# LumiDrive.net
KiCad netlist of a schematic drawn in EAGLE
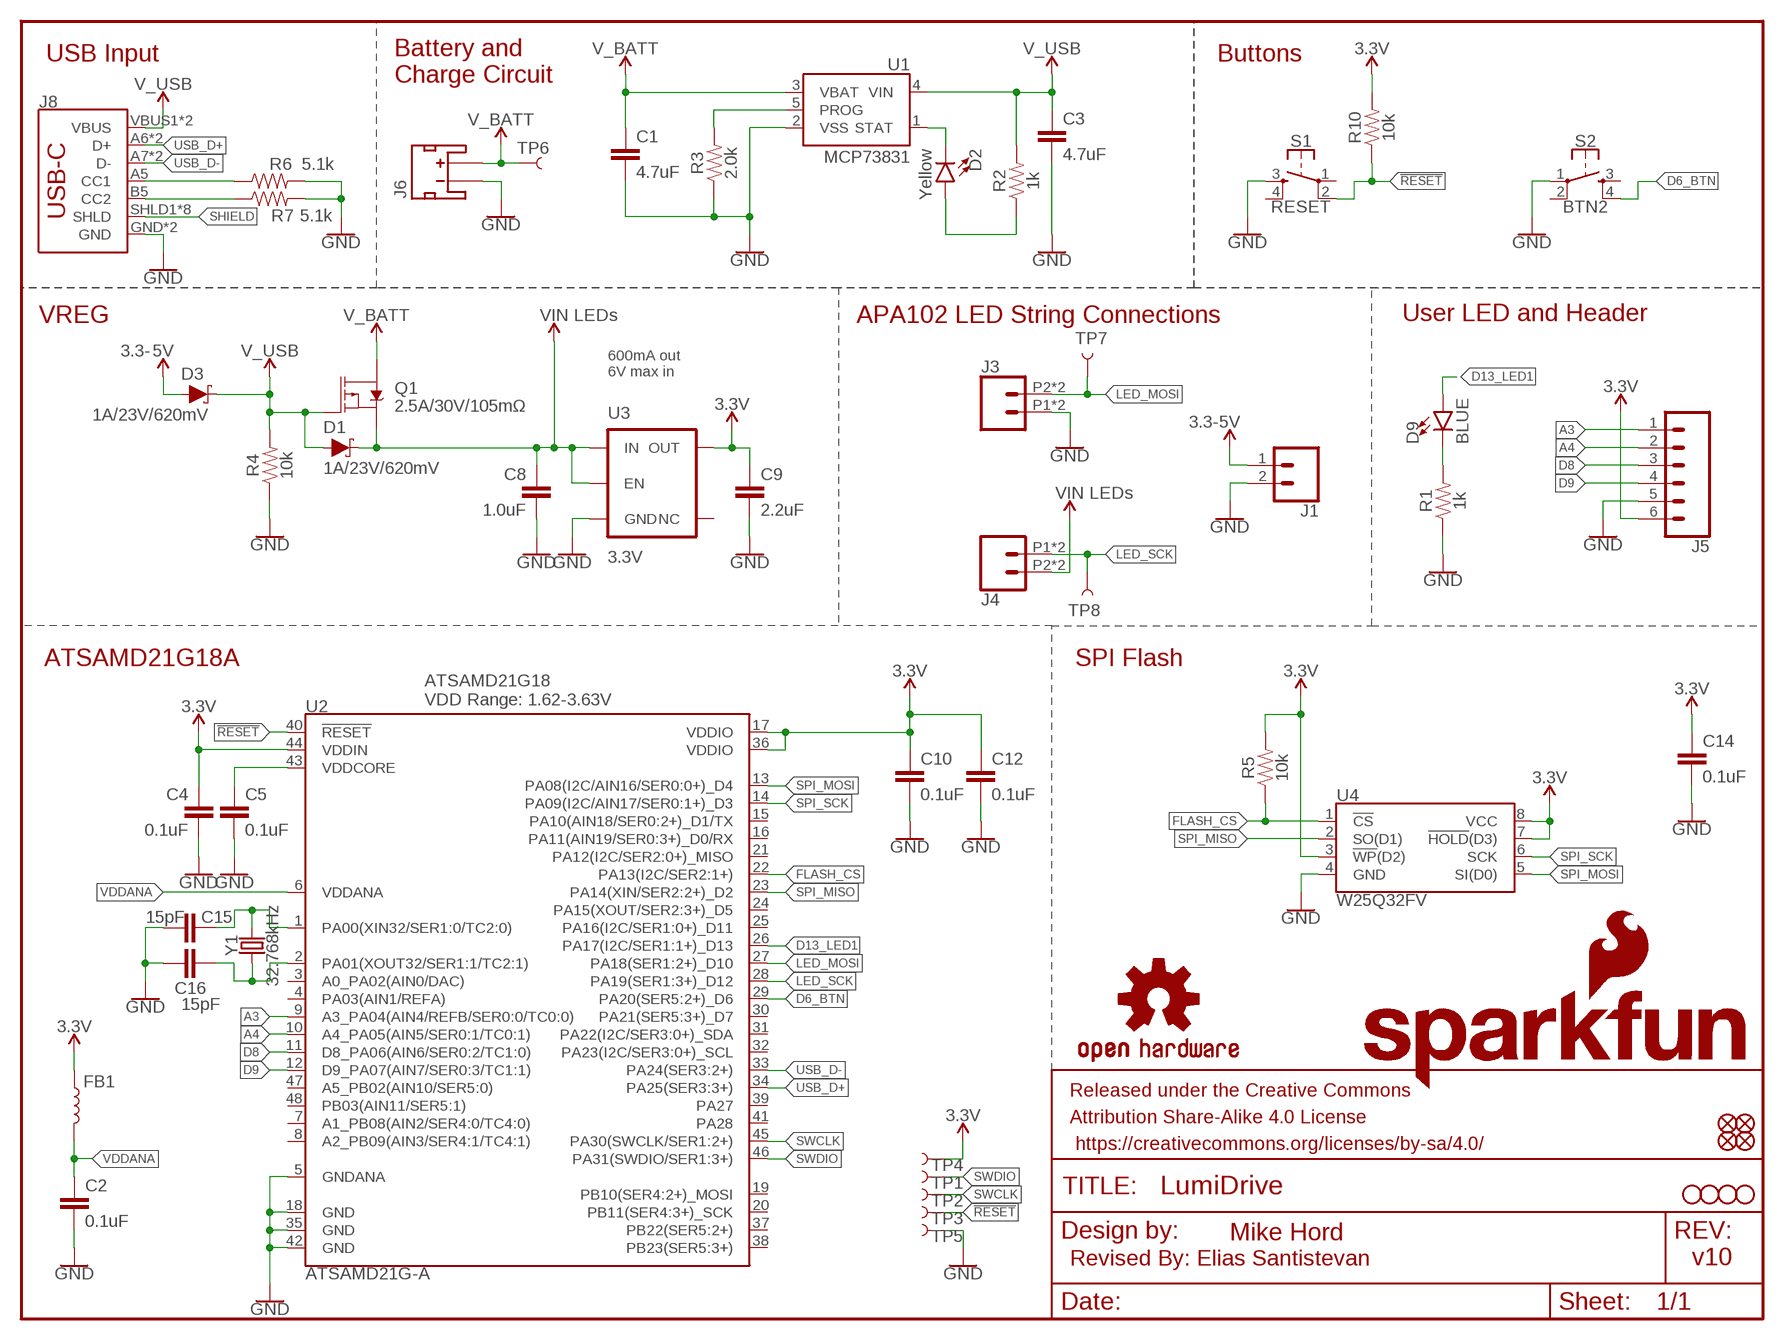
[diagram p0: schematic, sheet 1]

(export (version "E")
  (design (tool "Eeschema 10.0.6"))
  (components
    (comp (ref "C1")
      (value "4.7uF")
      (footprint "eagle-import:0603")
      (libsource (lib "eagle-import") (part "4.7UF-0603-6.3V-(10%)"))
    )
    (comp (ref "C2")
      (value "0.1uF")
      (footprint "eagle-import:0603")
      (libsource (lib "eagle-import") (part "0.1UF-0603-25V-(+80/-20%)"))
    )
    (comp (ref "C3")
      (value "4.7uF")
      (footprint "eagle-import:0603")
      (libsource (lib "eagle-import") (part "4.7UF-0603-6.3V-(10%)"))
    )
    (comp (ref "C4")
      (value "0.1uF")
      (footprint "eagle-import:0603")
      (libsource (lib "eagle-import") (part "0.1UF-0603-25V-(+80/-20%)"))
    )
    (comp (ref "C5")
      (value "0.1uF")
      (footprint "eagle-import:0603")
      (libsource (lib "eagle-import") (part "0.1UF-0603-25V-(+80/-20%)"))
    )
    (comp (ref "C8")
      (value "1.0uF")
      (footprint "eagle-import:0805")
      (libsource (lib "eagle-import") (part "1.0UF-0805-25V-10%"))
    )
    (comp (ref "C9")
      (value "2.2uF")
      (footprint "eagle-import:0603")
      (libsource (lib "eagle-import") (part "2.2UF-0603-10V-20%"))
    )
    (comp (ref "C10")
      (value "0.1uF")
      (footprint "eagle-import:0603")
      (libsource (lib "eagle-import") (part "0.1UF-0603-25V-(+80/-20%)"))
    )
    (comp (ref "C12")
      (value "0.1uF")
      (footprint "eagle-import:0603")
      (libsource (lib "eagle-import") (part "0.1UF-0603-25V-(+80/-20%)"))
    )
    (comp (ref "C14")
      (value "0.1uF")
      (footprint "eagle-import:0603")
      (libsource (lib "eagle-import") (part "0.1UF-0603-25V-(+80/-20%)"))
    )
    (comp (ref "C15")
      (value "15pF")
      (footprint "eagle-import:0603")
      (libsource (lib "eagle-import") (part "15PF-0603-50V-5%"))
    )
    (comp (ref "C16")
      (value "15pF")
      (footprint "eagle-import:0603")
      (libsource (lib "eagle-import") (part "15PF-0603-50V-5%"))
    )
    (comp (ref "D1")
      (value "1A/23V/620mV")
      (footprint "eagle-import:SOD-323")
      (libsource (lib "eagle-import") (part "DIODE-SCHOTTKY-BAT20J"))
    )
    (comp (ref "D2")
      (value "Yellow")
      (footprint "eagle-import:LED-0603")
      (libsource (lib "eagle-import") (part "LED-YELLOW0603"))
    )
    (comp (ref "D3")
      (value "1A/23V/620mV")
      (footprint "eagle-import:SOD-323")
      (libsource (lib "eagle-import") (part "DIODE-SCHOTTKY-BAT20J"))
    )
    (comp (ref "D9")
      (value "BLUE")
      (footprint "eagle-import:LED-0603")
      (libsource (lib "eagle-import") (part "LED-BLUE0603"))
    )
    (comp (ref "FB1")
      (value "30Ω/1.8A")
      (footprint "eagle-import:0603")
      (libsource (lib "eagle-import") (part "INDUCTORFB-30OHM"))
    )
    (comp (ref "FD1")
      (value "FIDUCIALUFIDUCIAL")
      (footprint "eagle-import:FIDUCIAL-MICRO")
      (libsource (lib "eagle-import") (part "FIDUCIALUFIDUCIAL"))
    )
    (comp (ref "FD2")
      (value "FIDUCIALUFIDUCIAL")
      (footprint "eagle-import:FIDUCIAL-MICRO")
      (libsource (lib "eagle-import") (part "FIDUCIALUFIDUCIAL"))
    )
    (comp (ref "FD3")
      (value "FIDUCIALUFIDUCIAL")
      (footprint "eagle-import:FIDUCIAL-MICRO")
      (libsource (lib "eagle-import") (part "FIDUCIALUFIDUCIAL"))
    )
    (comp (ref "FD4")
      (value "FIDUCIALUFIDUCIAL")
      (footprint "eagle-import:FIDUCIAL-MICRO")
      (libsource (lib "eagle-import") (part "FIDUCIALUFIDUCIAL"))
    )
    (comp (ref "FRAME1")
      (value "FRAME-LETTER")
      (footprint "eagle-import:CREATIVE_COMMONS")
      (libsource (lib "eagle-import") (part "FRAME-LETTER"))
    )
    (comp (ref "H1")
      (value "STAND-OFF")
      (footprint "eagle-import:STAND-OFF")
      (libsource (lib "eagle-import") (part "STAND-OFF"))
    )
    (comp (ref "H2")
      (value "STAND-OFF")
      (footprint "eagle-import:STAND-OFF")
      (libsource (lib "eagle-import") (part "STAND-OFF"))
    )
    (comp (ref "H3")
      (value "STAND-OFF")
      (footprint "eagle-import:STAND-OFF")
      (libsource (lib "eagle-import") (part "STAND-OFF"))
    )
    (comp (ref "H4")
      (value "STAND-OFF")
      (footprint "eagle-import:STAND-OFF")
      (libsource (lib "eagle-import") (part "STAND-OFF"))
    )
    (comp (ref "J1")
      (value "CONN_021X02_NO_SILK")
      (footprint "eagle-import:1X02_NO_SILK")
      (libsource (lib "eagle-import") (part "CONN_021X02_NO_SILK"))
    )
    (comp (ref "J3")
      (value "CONN_02SMALL_POKEHOME")
      (footprint "eagle-import:1X02_POKEHOME")
      (libsource (lib "eagle-import") (part "CONN_02SMALL_POKEHOME"))
    )
    (comp (ref "J4")
      (value "CONN_02SMALL_POKEHOME")
      (footprint "eagle-import:1X02_POKEHOME")
      (libsource (lib "eagle-import") (part "CONN_02SMALL_POKEHOME"))
    )
    (comp (ref "J5")
      (value "CONN_06NO_SILK_FEMALE_PTH")
      (footprint "eagle-import:1X06_NO_SILK")
      (libsource (lib "eagle-import") (part "CONN_06NO_SILK_FEMALE_PTH"))
    )
    (comp (ref "J6")
      (value "JST_2MM_MALE")
      (footprint "eagle-import:JST-2-SMD")
      (libsource (lib "eagle-import") (part "JST_2MM_MALE"))
    )
    (comp (ref "J8")
      (value "USB_C16PIN")
      (footprint "eagle-import:USB-C-16P")
      (libsource (lib "eagle-import") (part "USB_C16PIN"))
    )
    (comp (ref "LOGO1")
      (value "OSHW-LOGOM")
      (footprint "eagle-import:OSHW-LOGO-M")
      (libsource (lib "eagle-import") (part "OSHW-LOGOM"))
    )
    (comp (ref "LOGO3")
      (value "SFE_LOGO_NAME_FLAME.2_INCH")
      (footprint "eagle-import:SFE_LOGO_NAME_FLAME_.2")
      (libsource (lib "eagle-import") (part "SFE_LOGO_NAME_FLAME.2_INCH"))
    )
    (comp (ref "Q1")
      (value "2.5A/30V/105mΩ")
      (footprint "eagle-import:SOT23-3")
      (libsource (lib "eagle-import") (part "MOSFET_PCH-DMG2307L"))
    )
    (comp (ref "R1")
      (value "1k")
      (footprint "eagle-import:0603")
      (libsource (lib "eagle-import") (part "1KOHM-0603-1/10W-1%"))
    )
    (comp (ref "R2")
      (value "1k")
      (footprint "eagle-import:0603")
      (libsource (lib "eagle-import") (part "1KOHM-0603-1/10W-1%"))
    )
    (comp (ref "R3")
      (value "2.0k")
      (footprint "eagle-import:0603")
      (libsource (lib "eagle-import") (part "2.0KOHM-0603-1/10W-5%"))
    )
    (comp (ref "R4")
      (value "10k")
      (footprint "eagle-import:0603")
      (libsource (lib "eagle-import") (part "10KOHM-0603-1/10W-1%"))
    )
    (comp (ref "R5")
      (value "10k")
      (footprint "eagle-import:0603")
      (libsource (lib "eagle-import") (part "10KOHM-0603-1/10W-1%"))
    )
    (comp (ref "R6")
      (value "5.1k")
      (footprint "eagle-import:0603")
      (libsource (lib "eagle-import") (part "5.1KOHM5.1KOHM-0603-1/10W-1%"))
    )
    (comp (ref "R7")
      (value "5.1k")
      (footprint "eagle-import:0603")
      (libsource (lib "eagle-import") (part "5.1KOHM5.1KOHM-0603-1/10W-1%"))
    )
    (comp (ref "R10")
      (value "10k")
      (footprint "eagle-import:0603")
      (libsource (lib "eagle-import") (part "10KOHM-0603-1/10W-1%"))
    )
    (comp (ref "S1")
      (value "RESET")
      (footprint "eagle-import:TACTILE_SWITCH_SMD_4.6X2.8MM")
      (libsource (lib "eagle-import") (part "MOMENTARY-SWITCH-SPST-2-SMD-4.6X2.8MM"))
    )
    (comp (ref "S2")
      (value "BTN2")
      (footprint "eagle-import:TACTILE_SWITCH_SMD_4.6X2.8MM")
      (libsource (lib "eagle-import") (part "MOMENTARY-SWITCH-SPST-2-SMD-4.6X2.8MM"))
    )
    (comp (ref "TP1")
      (value "TP-SWDIO")
      (footprint "eagle-import:PAD.03X.05")
      (libsource (lib "eagle-import") (part "TEST-POINT3X5"))
    )
    (comp (ref "TP2")
      (value "TP-SWCLK")
      (footprint "eagle-import:PAD.03X.05")
      (libsource (lib "eagle-import") (part "TEST-POINT3X5"))
    )
    (comp (ref "TP3")
      (value "TP-!RESET!")
      (footprint "eagle-import:PAD.03X.05")
      (libsource (lib "eagle-import") (part "TEST-POINT3X5"))
    )
    (comp (ref "TP4")
      (value "TP-3.3V")
      (footprint "eagle-import:PAD.03X.05")
      (libsource (lib "eagle-import") (part "TEST-POINT3X5"))
    )
    (comp (ref "TP5")
      (value "TP-GND")
      (footprint "eagle-import:PAD.03X.05")
      (libsource (lib "eagle-import") (part "TEST-POINT3X5"))
    )
    (comp (ref "TP6")
      (value "TEST-POINT3X4")
      (footprint "eagle-import:PAD.03X.04")
      (libsource (lib "eagle-import") (part "TEST-POINT3X4"))
    )
    (comp (ref "TP7")
      (value "TEST-POINT3X4")
      (footprint "eagle-import:PAD.03X.04")
      (libsource (lib "eagle-import") (part "TEST-POINT3X4"))
    )
    (comp (ref "TP8")
      (value "TEST-POINT3X4")
      (footprint "eagle-import:PAD.03X.04")
      (libsource (lib "eagle-import") (part "TEST-POINT3X4"))
    )
    (comp (ref "U1")
      (value "MCP73831")
      (footprint "eagle-import:SOT23-5")
      (libsource (lib "eagle-import") (part "MCP73831"))
    )
    (comp (ref "U2")
      (value "ATSAMD21G-A")
      (footprint "eagle-import:TQFP-48")
      (libsource (lib "eagle-import") (part "ATSAMD21G-A"))
    )
    (comp (ref "U3")
      (value "3.3V")
      (footprint "eagle-import:SOT23-5")
      (fields (field (name "PROD_ID") "VREG-12457"))
      (libsource (lib "eagle-import") (part "V_REG_AP2112K-3.3V"))
    )
    (comp (ref "U4")
      (value "W25Q32FV")
      (footprint "eagle-import:SOIC-8")
      (libsource (lib "eagle-import") (part "W25Q32FVSS"))
    )
    (comp (ref "Y1")
      (value "32.768kHz")
      (footprint "eagle-import:CRYSTAL-SMD-3.2X1.5MM")
      (libsource (lib "eagle-import") (part "CRYSTAL-32.768KHZSMD-3.2X1.5"))
    )
  )
  (nets
    (net (code "1") (name "/~{RESET}") (class "Default")
      (node (ref "R10") (pin "1") (pinfunction "1_1") (pintype "passive"))
      (node (ref "S1") (pin "2") (pinfunction "2_2") (pintype "passive"))
      (node (ref "TP3") (pin "P$1") (pinfunction "1_P$1") (pintype "bidirectional"))
      (node (ref "U2") (pin "40") (pinfunction "~{RESET}_40") (pintype "bidirectional"))
    )
    (net (code "2") (name "3.3V") (class "Default")
      (node (ref "C10") (pin "1") (pinfunction "1_1") (pintype "passive"))
      (node (ref "C12") (pin "1") (pinfunction "1_1") (pintype "passive"))
      (node (ref "C14") (pin "1") (pinfunction "1_1") (pintype "passive"))
      (node (ref "C4") (pin "1") (pinfunction "1_1") (pintype "passive"))
      (node (ref "C9") (pin "1") (pinfunction "1_1") (pintype "passive"))
      (node (ref "FB1") (pin "1") (pinfunction "1_1") (pintype "passive"))
      (node (ref "J5") (pin "6") (pinfunction "6_6") (pintype "passive"))
      (node (ref "R10") (pin "2") (pinfunction "2_2") (pintype "passive"))
      (node (ref "R5") (pin "2") (pinfunction "2_2") (pintype "passive"))
      (node (ref "TP4") (pin "P$1") (pinfunction "1_P$1") (pintype "bidirectional"))
      (node (ref "U2") (pin "17") (pinfunction "VDDIO_17") (pintype "bidirectional"))
      (node (ref "U2") (pin "36") (pinfunction "VDDIO_36") (pintype "bidirectional"))
      (node (ref "U2") (pin "44") (pinfunction "VDDIN_44") (pintype "bidirectional"))
      (node (ref "U3") (pin "5") (pinfunction "OUT_5") (pintype "passive"))
      (node (ref "U4") (pin "3") (pinfunction "~{WP}(D2)_3") (pintype "bidirectional"))
      (node (ref "U4") (pin "7") (pinfunction "~{HOLD}(D3)_7") (pintype "bidirectional"))
      (node (ref "U4") (pin "8") (pinfunction "VCC_8") (pintype "bidirectional"))
    )
    (net (code "3") (name "5V") (class "Default")
      (node (ref "D3") (pin "A") (pinfunction "A_A") (pintype "passive"))
      (node (ref "J1") (pin "1") (pinfunction "1_1") (pintype "passive"))
    )
    (net (code "4") (name "A3") (class "Default")
      (node (ref "J5") (pin "1") (pinfunction "1_1") (pintype "passive"))
      (node (ref "U2") (pin "9") (pinfunction "A3_PA04(AIN4/REFB/SER0:0/TC0:0)_9") (pintype "bidirectional"))
    )
    (net (code "5") (name "A4") (class "Default")
      (node (ref "J5") (pin "2") (pinfunction "2_2") (pintype "passive"))
      (node (ref "U2") (pin "10") (pinfunction "A4_PA05(AIN5/SER0:1/TC0:1)_10") (pintype "bidirectional"))
    )
    (net (code "6") (name "D6_BTN") (class "Default")
      (node (ref "S2") (pin "4") (pinfunction "4_4") (pintype "passive"))
      (node (ref "U2") (pin "29") (pinfunction "PA20(SER5:2+)_D6_29") (pintype "bidirectional"))
    )
    (net (code "7") (name "D8") (class "Default")
      (node (ref "J5") (pin "3") (pinfunction "3_3") (pintype "passive"))
      (node (ref "U2") (pin "11") (pinfunction "D8_PA06(AIN6/SER0:2/TC1:0)_11") (pintype "bidirectional"))
    )
    (net (code "8") (name "D9") (class "Default")
      (node (ref "J5") (pin "4") (pinfunction "4_4") (pintype "passive"))
      (node (ref "U2") (pin "12") (pinfunction "D9_PA07(AIN7/SER0:3/TC1:1)_12") (pintype "bidirectional"))
    )
    (net (code "9") (name "D13_LED1") (class "Default")
      (node (ref "D9") (pin "A") (pinfunction "A_A") (pintype "passive"))
      (node (ref "U2") (pin "26") (pinfunction "PA17(I2C/SER1:1+)_D13_26") (pintype "bidirectional"))
    )
    (net (code "10") (name "FLASH_CS") (class "Default")
      (node (ref "R5") (pin "1") (pinfunction "1_1") (pintype "passive"))
      (node (ref "U2") (pin "22") (pinfunction "PA13(I2C/SER2:1+)_22") (pintype "bidirectional"))
      (node (ref "U4") (pin "1") (pinfunction "~{CS}_1") (pintype "bidirectional"))
    )
    (net (code "11") (name "GND") (class "Default")
      (node (ref "C1") (pin "2") (pinfunction "2_2") (pintype "passive"))
      (node (ref "C10") (pin "2") (pinfunction "2_2") (pintype "passive"))
      (node (ref "C12") (pin "2") (pinfunction "2_2") (pintype "passive"))
      (node (ref "C14") (pin "2") (pinfunction "2_2") (pintype "passive"))
      (node (ref "C15") (pin "1") (pinfunction "1_1") (pintype "passive"))
      (node (ref "C16") (pin "1") (pinfunction "1_1") (pintype "passive"))
      (node (ref "C2") (pin "2") (pinfunction "2_2") (pintype "passive"))
      (node (ref "C3") (pin "2") (pinfunction "2_2") (pintype "passive"))
      (node (ref "C4") (pin "2") (pinfunction "2_2") (pintype "passive"))
      (node (ref "C5") (pin "2") (pinfunction "2_2") (pintype "passive"))
      (node (ref "C8") (pin "2") (pinfunction "2_2") (pintype "passive"))
      (node (ref "C9") (pin "2") (pinfunction "2_2") (pintype "passive"))
      (node (ref "J1") (pin "2") (pinfunction "2_2") (pintype "passive"))
      (node (ref "J3") (pin "P1") (pinfunction "1_P1") (pintype "passive"))
      (node (ref "J3") (pin "P3") (pinfunction "1_P3") (pintype "passive"))
      (node (ref "J5") (pin "5") (pinfunction "5_5") (pintype "passive"))
      (node (ref "J6") (pin "1") (pinfunction "-_1") (pintype "bidirectional"))
      (node (ref "J8") (pin "GND") (pinfunction "GND_GND") (pintype "bidirectional"))
      (node (ref "J8") (pin "GND2") (pinfunction "GND_GND2") (pintype "bidirectional"))
      (node (ref "R1") (pin "1") (pinfunction "1_1") (pintype "passive"))
      (node (ref "R3") (pin "1") (pinfunction "1_1") (pintype "passive"))
      (node (ref "R4") (pin "1") (pinfunction "1_1") (pintype "passive"))
      (node (ref "R6") (pin "2") (pinfunction "2_2") (pintype "passive"))
      (node (ref "R7") (pin "2") (pinfunction "2_2") (pintype "passive"))
      (node (ref "S1") (pin "3") (pinfunction "3_3") (pintype "passive"))
      (node (ref "S2") (pin "1") (pinfunction "1_1") (pintype "passive"))
      (node (ref "TP5") (pin "P$1") (pinfunction "1_P$1") (pintype "bidirectional"))
      (node (ref "U1") (pin "2") (pinfunction "VSS_2") (pintype "power_in"))
      (node (ref "U2") (pin "18") (pinfunction "GND_18") (pintype "bidirectional"))
      (node (ref "U2") (pin "35") (pinfunction "GND_35") (pintype "bidirectional"))
      (node (ref "U2") (pin "42") (pinfunction "GND_42") (pintype "bidirectional"))
      (node (ref "U2") (pin "5") (pinfunction "GNDANA_5") (pintype "bidirectional"))
      (node (ref "U3") (pin "2") (pinfunction "GND_2") (pintype "input"))
      (node (ref "U4") (pin "4") (pinfunction "GND_4") (pintype "bidirectional"))
    )
    (net (code "12") (name "LED_MOSI") (class "Default")
      (node (ref "J3") (pin "P2") (pinfunction "2_P2") (pintype "passive"))
      (node (ref "J3") (pin "P4") (pinfunction "2_P4") (pintype "passive"))
      (node (ref "TP7") (pin "P$1") (pinfunction "1_P$1") (pintype "bidirectional"))
      (node (ref "U2") (pin "27") (pinfunction "PA18(SER1:2+)_D10_27") (pintype "bidirectional"))
    )
    (net (code "13") (name "LED_SCK") (class "Default")
      (node (ref "J4") (pin "P1") (pinfunction "1_P1") (pintype "passive"))
      (node (ref "J4") (pin "P3") (pinfunction "1_P3") (pintype "passive"))
      (node (ref "TP8") (pin "P$1") (pinfunction "1_P$1") (pintype "bidirectional"))
      (node (ref "U2") (pin "28") (pinfunction "PA19(SER1:3+)_D12_28") (pintype "bidirectional"))
    )
    (net (code "14") (name "Net-(D2-PadA)") (class "Default")
      (node (ref "D2") (pin "A") (pinfunction "A_A") (pintype "passive"))
      (node (ref "R2") (pin "1") (pinfunction "1_1") (pintype "passive"))
    )
    (net (code "15") (name "Net-(D9-PadC)") (class "Default")
      (node (ref "D9") (pin "C") (pinfunction "C_C") (pintype "passive"))
      (node (ref "R1") (pin "2") (pinfunction "2_2") (pintype "passive"))
    )
    (net (code "16") (name "Net-(J8-CC1)") (class "Default")
      (node (ref "J8") (pin "A5") (pinfunction "CC1_A5") (pintype "bidirectional"))
      (node (ref "R6") (pin "1") (pinfunction "1_1") (pintype "passive"))
    )
    (net (code "17") (name "Net-(J8-CC2)") (class "Default")
      (node (ref "J8") (pin "B5") (pinfunction "CC2_B5") (pintype "bidirectional"))
      (node (ref "R7") (pin "1") (pinfunction "1_1") (pintype "passive"))
    )
    (net (code "18") (name "Net-(U1-PROG)") (class "Default")
      (node (ref "R3") (pin "2") (pinfunction "2_2") (pintype "passive"))
      (node (ref "U1") (pin "5") (pinfunction "PROG_5") (pintype "input"))
    )
    (net (code "19") (name "Net-(U1-STAT)") (class "Default")
      (node (ref "D2") (pin "C") (pinfunction "C_C") (pintype "passive"))
      (node (ref "U1") (pin "1") (pinfunction "STAT_1") (pintype "output"))
    )
    (net (code "20") (name "Net-(U2-PA00(XIN32{slash}SER1:0{slash}TC2:0))") (class "Default")
      (node (ref "C15") (pin "2") (pinfunction "2_2") (pintype "passive"))
      (node (ref "U2") (pin "1") (pinfunction "PA00(XIN32/SER1:0/TC2:0)_1") (pintype "bidirectional"))
      (node (ref "Y1") (pin "P$2") (pinfunction "2_P$2") (pintype "passive"))
    )
    (net (code "21") (name "Net-(U2-PA01(XOUT32{slash}SER1:1{slash}TC2:1))") (class "Default")
      (node (ref "C16") (pin "2") (pinfunction "2_2") (pintype "passive"))
      (node (ref "U2") (pin "2") (pinfunction "PA01(XOUT32/SER1:1/TC2:1)_2") (pintype "bidirectional"))
      (node (ref "Y1") (pin "P$1") (pinfunction "1_P$1") (pintype "passive"))
    )
    (net (code "22") (name "Net-(U2-VDDCORE)") (class "Default")
      (node (ref "C5") (pin "1") (pinfunction "1_1") (pintype "passive"))
      (node (ref "U2") (pin "43") (pinfunction "VDDCORE_43") (pintype "bidirectional"))
    )
    (net (code "23") (name "SHIELD") (class "Default")
      (node (ref "J8") (pin "SHLD1") (pinfunction "SHLD_SHLD1") (pintype "bidirectional"))
      (node (ref "J8") (pin "SHLD2") (pinfunction "SHLD_SHLD2") (pintype "bidirectional"))
      (node (ref "J8") (pin "SHLD3") (pinfunction "SHLD_SHLD3") (pintype "bidirectional"))
      (node (ref "J8") (pin "SHLD4") (pinfunction "SHLD_SHLD4") (pintype "bidirectional"))
      (node (ref "J8") (pin "SHLD5") (pinfunction "SHLD_SHLD5") (pintype "bidirectional"))
      (node (ref "J8") (pin "SHLD6") (pinfunction "SHLD_SHLD6") (pintype "bidirectional"))
      (node (ref "J8") (pin "SHLD7") (pinfunction "SHLD_SHLD7") (pintype "bidirectional"))
      (node (ref "J8") (pin "SHLD8") (pinfunction "SHLD_SHLD8") (pintype "bidirectional"))
    )
    (net (code "24") (name "SPI_MISO") (class "Default")
      (node (ref "U2") (pin "23") (pinfunction "PA14(XIN/SER2:2+)_D2_23") (pintype "bidirectional"))
      (node (ref "U4") (pin "2") (pinfunction "SO(D1)_2") (pintype "bidirectional"))
    )
    (net (code "25") (name "SPI_MOSI") (class "Default")
      (node (ref "U2") (pin "13") (pinfunction "PA08(I2C/AIN16/SER0:0+)_D4_13") (pintype "bidirectional"))
      (node (ref "U4") (pin "5") (pinfunction "SI(D0)_5") (pintype "bidirectional"))
    )
    (net (code "26") (name "SPI_SCK") (class "Default")
      (node (ref "U2") (pin "14") (pinfunction "PA09(I2C/AIN17/SER0:1+)_D3_14") (pintype "bidirectional"))
      (node (ref "U4") (pin "6") (pinfunction "SCK_6") (pintype "bidirectional"))
    )
    (net (code "27") (name "SWCLK") (class "Default")
      (node (ref "TP2") (pin "P$1") (pinfunction "1_P$1") (pintype "bidirectional"))
      (node (ref "U2") (pin "45") (pinfunction "PA30(SWCLK/SER1:2+)_45") (pintype "bidirectional"))
    )
    (net (code "28") (name "SWDIO") (class "Default")
      (node (ref "TP1") (pin "P$1") (pinfunction "1_P$1") (pintype "bidirectional"))
      (node (ref "U2") (pin "46") (pinfunction "PA31(SWDIO/SER1:3+)_46") (pintype "bidirectional"))
    )
    (net (code "29") (name "USB_D+") (class "Default")
      (node (ref "J8") (pin "A6") (pinfunction "D+_A6") (pintype "bidirectional"))
      (node (ref "J8") (pin "B6") (pinfunction "D+_B6") (pintype "bidirectional"))
      (node (ref "U2") (pin "34") (pinfunction "PA25(SER3:3+)_34") (pintype "bidirectional"))
    )
    (net (code "30") (name "USB_D-") (class "Default")
      (node (ref "J8") (pin "A7") (pinfunction "D-_A7") (pintype "bidirectional"))
      (node (ref "J8") (pin "B7") (pinfunction "D-_B7") (pintype "bidirectional"))
      (node (ref "U2") (pin "33") (pinfunction "PA24(SER3:2+)_33") (pintype "bidirectional"))
    )
    (net (code "31") (name "VDDANA") (class "Default")
      (node (ref "C2") (pin "1") (pinfunction "1_1") (pintype "passive"))
      (node (ref "FB1") (pin "2") (pinfunction "2_2") (pintype "passive"))
      (node (ref "U2") (pin "6") (pinfunction "VDDANA_6") (pintype "bidirectional"))
    )
    (net (code "32") (name "VIN") (class "Default")
      (node (ref "C8") (pin "1") (pinfunction "1_1") (pintype "passive"))
      (node (ref "D1") (pin "C") (pinfunction "C_C") (pintype "passive"))
      (node (ref "J4") (pin "P2") (pinfunction "2_P2") (pintype "passive"))
      (node (ref "J4") (pin "P4") (pinfunction "2_P4") (pintype "passive"))
      (node (ref "Q1") (pin "2") (pinfunction "S_2") (pintype "bidirectional"))
      (node (ref "U3") (pin "1") (pinfunction "IN_1") (pintype "input"))
      (node (ref "U3") (pin "3") (pinfunction "EN_3") (pintype "input"))
    )
    (net (code "33") (name "V_BATT") (class "Default")
      (node (ref "C1") (pin "1") (pinfunction "1_1") (pintype "passive"))
      (node (ref "J6") (pin "2") (pinfunction "+_2") (pintype "bidirectional"))
      (node (ref "Q1") (pin "3") (pinfunction "D_3") (pintype "bidirectional"))
      (node (ref "TP6") (pin "P$1") (pinfunction "1_P$1") (pintype "bidirectional"))
      (node (ref "U1") (pin "3") (pinfunction "VBAT_3") (pintype "power_in"))
    )
    (net (code "34") (name "V_USB") (class "Default")
      (node (ref "C3") (pin "1") (pinfunction "1_1") (pintype "passive"))
      (node (ref "D1") (pin "A") (pinfunction "A_A") (pintype "passive"))
      (node (ref "D3") (pin "C") (pinfunction "C_C") (pintype "passive"))
      (node (ref "J8") (pin "VBUS1") (pinfunction "VBUS_VBUS1") (pintype "bidirectional"))
      (node (ref "J8") (pin "VBUS2") (pinfunction "VBUS_VBUS2") (pintype "bidirectional"))
      (node (ref "Q1") (pin "1") (pinfunction "G_1") (pintype "bidirectional"))
      (node (ref "R2") (pin "2") (pinfunction "2_2") (pintype "passive"))
      (node (ref "R4") (pin "2") (pinfunction "2_2") (pintype "passive"))
      (node (ref "U1") (pin "4") (pinfunction "VIN_4") (pintype "power_in"))
    )
    (net (code "35") (name "unconnected-(J6-PAD1-PadNC1)") (class "Default")
      (node (ref "J6") (pin "NC1") (pinfunction "PAD1_NC1") (pintype "bidirectional"))
    )
    (net (code "36") (name "unconnected-(J6-PAD2-PadNC2)") (class "Default")
      (node (ref "J6") (pin "NC2") (pinfunction "PAD2_NC2") (pintype "bidirectional"))
    )
    (net (code "37") (name "unconnected-(S1-Pad1)") (class "Default")
      (node (ref "S1") (pin "1") (pinfunction "1_1") (pintype "passive"))
    )
    (net (code "38") (name "unconnected-(S1-Pad4)") (class "Default")
      (node (ref "S1") (pin "4") (pinfunction "4_4") (pintype "passive"))
    )
    (net (code "39") (name "unconnected-(S2-Pad2)") (class "Default")
      (node (ref "S2") (pin "2") (pinfunction "2_2") (pintype "passive"))
    )
    (net (code "40") (name "unconnected-(S2-Pad3)") (class "Default")
      (node (ref "S2") (pin "3") (pinfunction "3_3") (pintype "passive"))
    )
    (net (code "41") (name "unconnected-(U2-A0_PA02(AIN0{slash}DAC)-Pad3)") (class "Default")
      (node (ref "U2") (pin "3") (pinfunction "A0_PA02(AIN0/DAC)_3") (pintype "bidirectional"))
    )
    (net (code "42") (name "unconnected-(U2-A1_PB08(AIN2{slash}SER4:0{slash}TC4:0)-Pad7)") (class "Default")
      (node (ref "U2") (pin "7") (pinfunction "A1_PB08(AIN2/SER4:0/TC4:0)_7") (pintype "bidirectional"))
    )
    (net (code "43") (name "unconnected-(U2-A2_PB09(AIN3{slash}SER4:1{slash}TC4:1)-Pad8)") (class "Default")
      (node (ref "U2") (pin "8") (pinfunction "A2_PB09(AIN3/SER4:1/TC4:1)_8") (pintype "bidirectional"))
    )
    (net (code "44") (name "unconnected-(U2-A5_PB02(AIN10{slash}SER5:0)-Pad47)") (class "Default")
      (node (ref "U2") (pin "47") (pinfunction "A5_PB02(AIN10/SER5:0)_47") (pintype "bidirectional"))
    )
    (net (code "45") (name "unconnected-(U2-PA03(AIN1{slash}REFA)-Pad4)") (class "Default")
      (node (ref "U2") (pin "4") (pinfunction "PA03(AIN1/REFA)_4") (pintype "bidirectional"))
    )
    (net (code "46") (name "unconnected-(U2-PA10(AIN18{slash}SER0:2+)_D1{slash}TX-Pad15)") (class "Default")
      (node (ref "U2") (pin "15") (pinfunction "PA10(AIN18/SER0:2+)_D1/TX_15") (pintype "bidirectional"))
    )
    (net (code "47") (name "unconnected-(U2-PA11(AIN19{slash}SER0:3+)_D0{slash}RX-Pad16)") (class "Default")
      (node (ref "U2") (pin "16") (pinfunction "PA11(AIN19/SER0:3+)_D0/RX_16") (pintype "bidirectional"))
    )
    (net (code "48") (name "unconnected-(U2-PA12(I2C{slash}SER2:0+)_MISO-Pad21)") (class "Default")
      (node (ref "U2") (pin "21") (pinfunction "PA12(I2C/SER2:0+)_MISO_21") (pintype "bidirectional"))
    )
    (net (code "49") (name "unconnected-(U2-PA15(XOUT{slash}SER2:3+)_D5-Pad24)") (class "Default")
      (node (ref "U2") (pin "24") (pinfunction "PA15(XOUT/SER2:3+)_D5_24") (pintype "bidirectional"))
    )
    (net (code "50") (name "unconnected-(U2-PA16(I2C{slash}SER1:0+)_D11-Pad25)") (class "Default")
      (node (ref "U2") (pin "25") (pinfunction "PA16(I2C/SER1:0+)_D11_25") (pintype "bidirectional"))
    )
    (net (code "51") (name "unconnected-(U2-PA21(SER5:3+)_D7-Pad30)") (class "Default")
      (node (ref "U2") (pin "30") (pinfunction "PA21(SER5:3+)_D7_30") (pintype "bidirectional"))
    )
    (net (code "52") (name "unconnected-(U2-PA22(I2C{slash}SER3:0+)_SDA-Pad31)") (class "Default")
      (node (ref "U2") (pin "31") (pinfunction "PA22(I2C/SER3:0+)_SDA_31") (pintype "bidirectional"))
    )
    (net (code "53") (name "unconnected-(U2-PA23(I2C{slash}SER3:0+)_SCL-Pad32)") (class "Default")
      (node (ref "U2") (pin "32") (pinfunction "PA23(I2C/SER3:0+)_SCL_32") (pintype "bidirectional"))
    )
    (net (code "54") (name "unconnected-(U2-PA27-Pad39)") (class "Default")
      (node (ref "U2") (pin "39") (pinfunction "PA27_39") (pintype "bidirectional"))
    )
    (net (code "55") (name "unconnected-(U2-PA28-Pad41)") (class "Default")
      (node (ref "U2") (pin "41") (pinfunction "PA28_41") (pintype "bidirectional"))
    )
    (net (code "56") (name "unconnected-(U2-PB03(AIN11{slash}SER5:1)-Pad48)") (class "Default")
      (node (ref "U2") (pin "48") (pinfunction "PB03(AIN11/SER5:1)_48") (pintype "bidirectional"))
    )
    (net (code "57") (name "unconnected-(U2-PB10(SER4:2+)_MOSI-Pad19)") (class "Default")
      (node (ref "U2") (pin "19") (pinfunction "PB10(SER4:2+)_MOSI_19") (pintype "bidirectional"))
    )
    (net (code "58") (name "unconnected-(U2-PB11(SER4:3+)_SCK-Pad20)") (class "Default")
      (node (ref "U2") (pin "20") (pinfunction "PB11(SER4:3+)_SCK_20") (pintype "bidirectional"))
    )
    (net (code "59") (name "unconnected-(U2-PB22(SER5:2+)-Pad37)") (class "Default")
      (node (ref "U2") (pin "37") (pinfunction "PB22(SER5:2+)_37") (pintype "bidirectional"))
    )
    (net (code "60") (name "unconnected-(U2-PB23(SER5:3+)-Pad38)") (class "Default")
      (node (ref "U2") (pin "38") (pinfunction "PB23(SER5:3+)_38") (pintype "bidirectional"))
    )
    (net (code "61") (name "unconnected-(U3-NC-Pad4)") (class "Default")
      (node (ref "U3") (pin "4") (pinfunction "NC_4") (pintype "no_connect"))
    )
  )
)
